# stellariscope.net
KiCad netlist of a schematic drawn in EAGLE
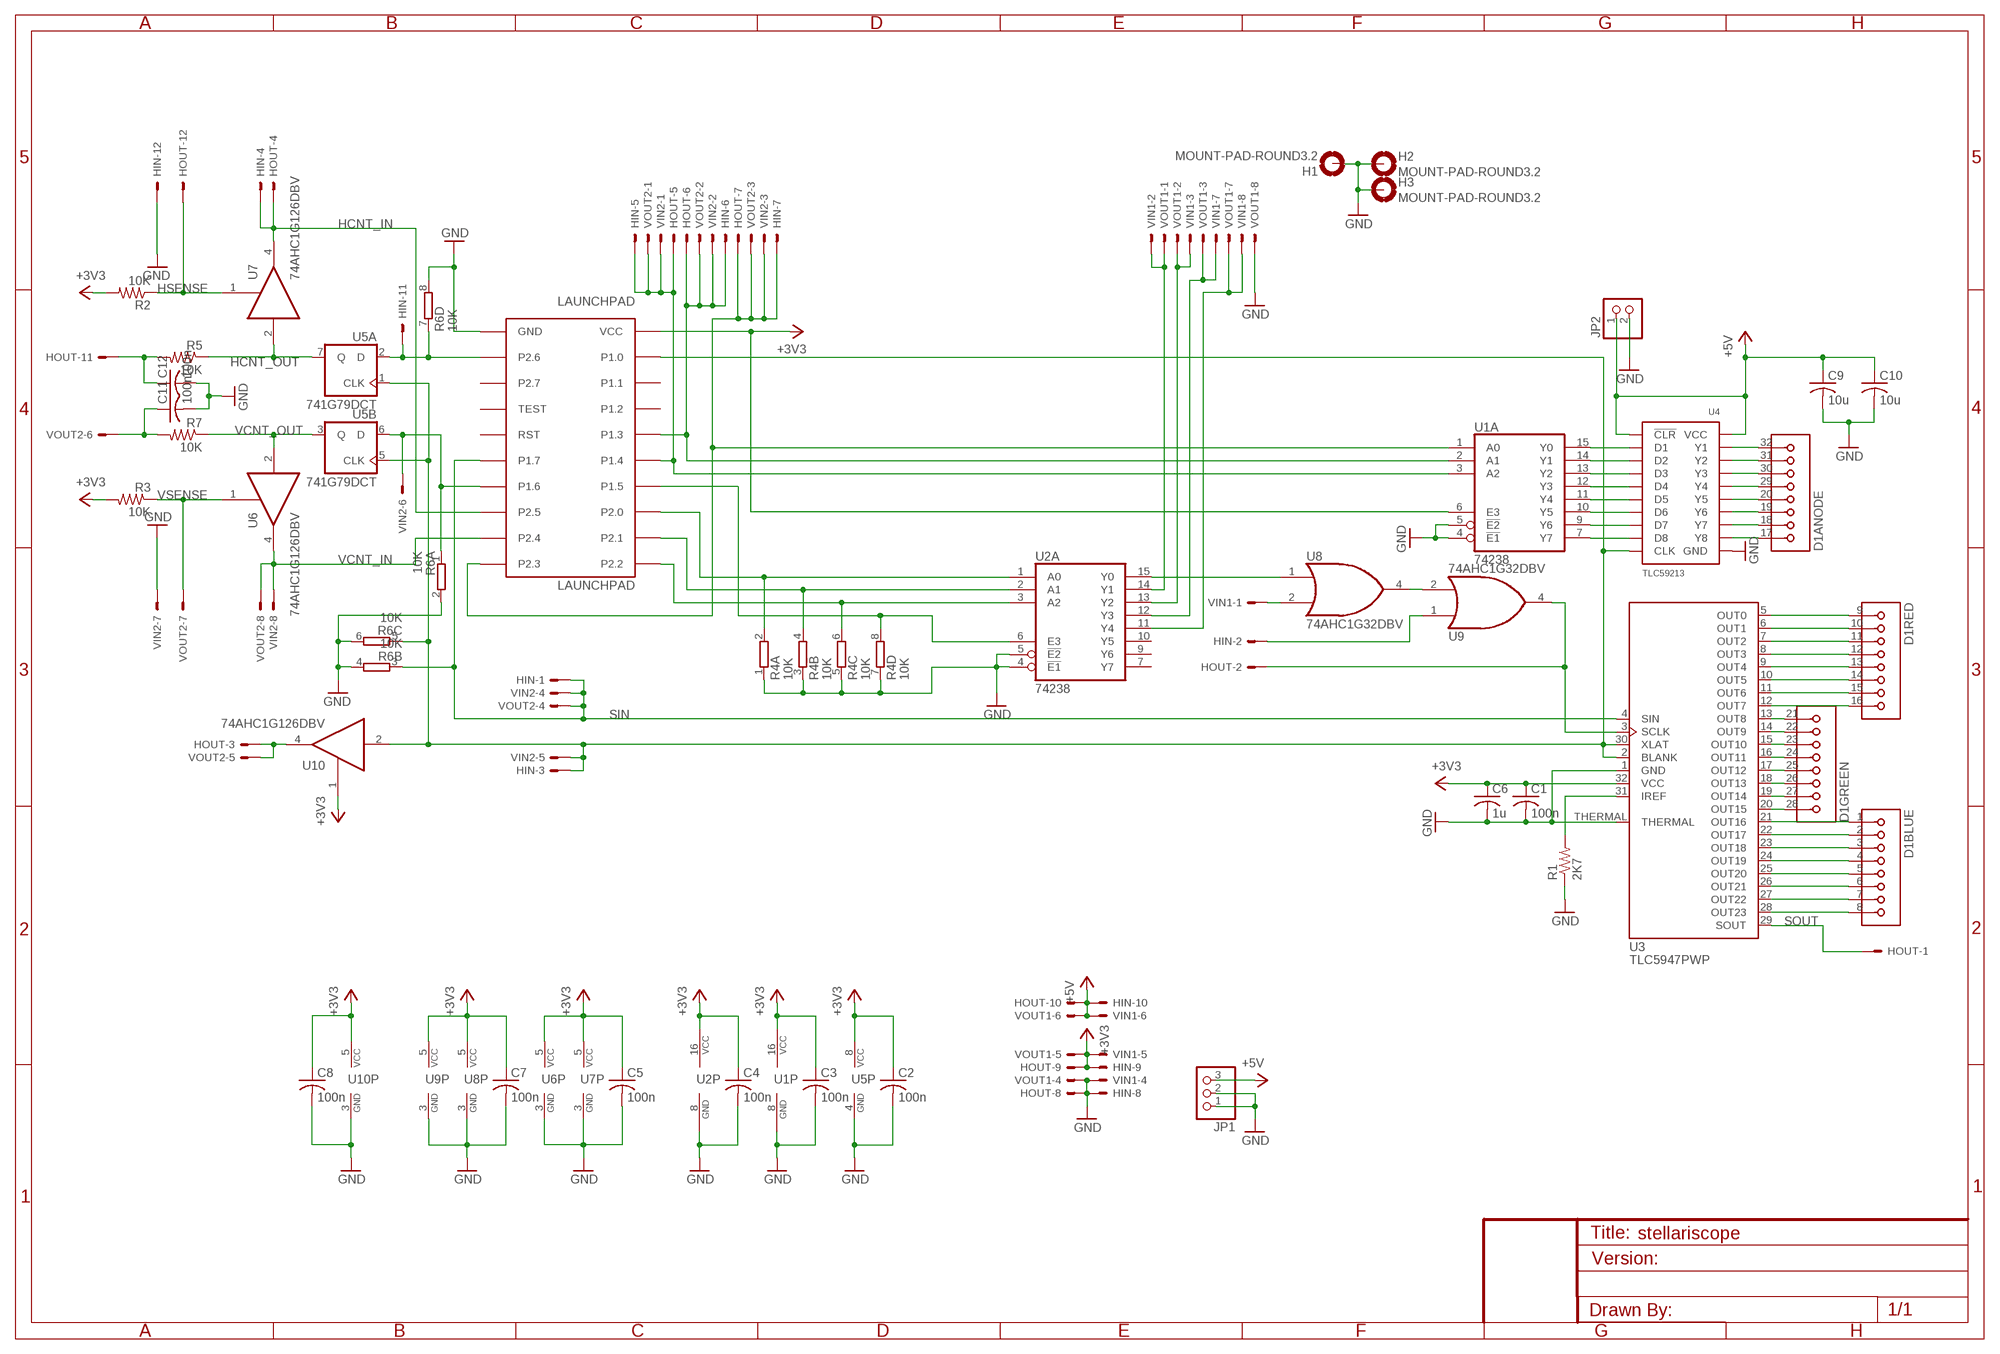
[diagram p0: schematic, sheet 1]

(export (version "E")
  (design (tool "Eeschema 10.0.6"))
  (components
    (comp (ref "C1")
      (value "100n")
      (footprint "eagle-import:C0603")
      (fields (field (name "PARTNO") "CC0603KRX7R9BB104"))
      (libsource (lib "eagle-import") (part "C-USC0603"))
    )
    (comp (ref "C2")
      (value "100n")
      (footprint "eagle-import:C0603")
      (fields (field (name "PARTNO") "CC0603KRX7R9BB104"))
      (libsource (lib "eagle-import") (part "C-USC0603"))
    )
    (comp (ref "C3")
      (value "100n")
      (footprint "eagle-import:C0603")
      (fields (field (name "PARTNO") "CC0603KRX7R9BB104"))
      (libsource (lib "eagle-import") (part "C-USC0603"))
    )
    (comp (ref "C4")
      (value "100n")
      (footprint "eagle-import:C0603")
      (fields (field (name "PARTNO") "CC0603KRX7R9BB104"))
      (libsource (lib "eagle-import") (part "C-USC0603"))
    )
    (comp (ref "C5")
      (value "100n")
      (footprint "eagle-import:C0603")
      (fields (field (name "PARTNO") "CC0603KRX7R9BB104"))
      (libsource (lib "eagle-import") (part "C-USC0603"))
    )
    (comp (ref "C6")
      (value "1u")
      (footprint "eagle-import:C0603")
      (fields (field (name "PARTNO") "C1608X5R1E105M"))
      (libsource (lib "eagle-import") (part "C-USC0603"))
    )
    (comp (ref "C7")
      (value "100n")
      (footprint "eagle-import:C0603")
      (fields (field (name "PARTNO") "CC0603KRX7R9BB104"))
      (libsource (lib "eagle-import") (part "C-USC0603"))
    )
    (comp (ref "C8")
      (value "100n")
      (footprint "eagle-import:C0603")
      (fields (field (name "PARTNO") "CC0603KRX7R9BB104"))
      (libsource (lib "eagle-import") (part "C-USC0603"))
    )
    (comp (ref "C9")
      (value "10u")
      (footprint "eagle-import:C1210")
      (fields (field (name "PARTNO") "C3216X5R1E106M"))
      (libsource (lib "eagle-import") (part "C-USC1210"))
    )
    (comp (ref "C10")
      (value "10u")
      (footprint "eagle-import:C1210")
      (fields (field (name "PARTNO") "C3216X5R1E106M"))
      (libsource (lib "eagle-import") (part "C-USC1210"))
    )
    (comp (ref "C11")
      (value "100n")
      (footprint "eagle-import:C0603")
      (fields (field (name "PARTNO") "CC0603KRX7R9BB104"))
      (libsource (lib "eagle-import") (part "C-USC0603"))
    )
    (comp (ref "C12")
      (value "100n")
      (footprint "eagle-import:C0603")
      (fields (field (name "PARTNO") "CC0603KRX7R9BB104"))
      (libsource (lib "eagle-import") (part "C-USC0603"))
    )
    (comp (ref "D1")
      (value "60MM-8X8-RGB-LED-ARRAY")
      (footprint "eagle-import:60MM-8X8-RGB-MATRIX")
      (fields (field (name "BOM") "EXCLUDE") (field (name "PARTNO") "*"))
      (libsource (lib "eagle-import") (part "60MM-8X8-RGB-LED-ARRAY"))
    )
    (comp (ref "H1")
      (value "MOUNT-PAD-ROUND3.2")
      (footprint "eagle-import:3,2-PAD")
      (libsource (lib "eagle-import") (part "MOUNT-PAD-ROUND3.2"))
    )
    (comp (ref "H2")
      (value "MOUNT-PAD-ROUND3.2")
      (footprint "eagle-import:3,2-PAD")
      (libsource (lib "eagle-import") (part "MOUNT-PAD-ROUND3.2"))
    )
    (comp (ref "H3")
      (value "MOUNT-PAD-ROUND3.2")
      (footprint "eagle-import:3,2-PAD")
      (libsource (lib "eagle-import") (part "MOUNT-PAD-ROUND3.2"))
    )
    (comp (ref "HIN")
      (value "87760-121")
      (footprint "eagle-import:87760-121")
      (fields (field (name "PARTNO") "87760-121"))
      (libsource (lib "eagle-import") (part "87760-121"))
    )
    (comp (ref "HOUT")
      (value "87264-125")
      (footprint "eagle-import:87264-125")
      (fields (field (name "PARTNO") "87264-125"))
      (libsource (lib "eagle-import") (part "87264-125"))
    )
    (comp (ref "JP1")
      (value "PINHD-1X3")
      (footprint "eagle-import:1X03")
      (libsource (lib "eagle-import") (part "PINHD-1X3"))
    )
    (comp (ref "JP2")
      (value "PINHD-1X2_2.54-90°")
      (footprint "eagle-import:1X02_90")
      (libsource (lib "eagle-import") (part "PINHD-1X2_2.54-90°"))
    )
    (comp (ref "LAUNCHPAD")
      (value "LAUNCHPAD")
      (footprint "eagle-import:LAUNCHPAD")
      (libsource (lib "eagle-import") (part "LAUNCHPAD"))
    )
    (comp (ref "R1")
      (value "2K7")
      (footprint "eagle-import:R0603")
      (fields (field (name "PARTNO") "RMCF0603FT2K70"))
      (libsource (lib "eagle-import") (part "R-US_R0603"))
    )
    (comp (ref "R2")
      (value "10K")
      (footprint "eagle-import:R0603")
      (fields (field (name "PARTNO") "RMCF0603FT10K0"))
      (libsource (lib "eagle-import") (part "R-US_R0603"))
    )
    (comp (ref "R3")
      (value "10K")
      (footprint "eagle-import:R0603")
      (fields (field (name "PARTNO") "RMCF0603FT10K0"))
      (libsource (lib "eagle-import") (part "R-US_R0603"))
    )
    (comp (ref "R4")
      (value "10K")
      (footprint "eagle-import:CTS742C083-RES")
      (fields (field (name "PARTNO") "742C083103JPTR"))
      (libsource (lib "eagle-import") (part "4R-NCTS742C083"))
    )
    (comp (ref "R5")
      (value "10K")
      (footprint "eagle-import:R0603")
      (fields (field (name "PARTNO") "RMCF0603FT10K0"))
      (libsource (lib "eagle-import") (part "R-US_R0603"))
    )
    (comp (ref "R6")
      (value "10K")
      (footprint "eagle-import:CTS742C083-RES")
      (fields (field (name "PARTNO") "742C083103JPTR"))
      (libsource (lib "eagle-import") (part "4R-NCTS742C083"))
    )
    (comp (ref "R7")
      (value "10K")
      (footprint "eagle-import:R0603")
      (fields (field (name "PARTNO") "RMCF0603FT10K0"))
      (libsource (lib "eagle-import") (part "R-US_R0603"))
    )
    (comp (ref "U1")
      (value "74238")
      (footprint "eagle-import:TSSOP16")
      (fields (field (name "PARTNO") "CD74HC238PWR"))
      (libsource (lib "eagle-import") (part "74238"))
    )
    (comp (ref "U2")
      (value "74238")
      (footprint "eagle-import:TSSOP16")
      (fields (field (name "PARTNO") "CD74HC238PWR"))
      (libsource (lib "eagle-import") (part "74238"))
    )
    (comp (ref "U3")
      (value "TLC5947PWP")
      (footprint "eagle-import:HTSSOP32-PWP")
      (fields (field (name "PARTNO") "TLC5947DAP"))
      (libsource (lib "eagle-import") (part "TLC5947PWP"))
    )
    (comp (ref "U4")
      (value "TLC59213")
      (footprint "eagle-import:TSSOP20")
      (fields (field (name "PARTNO") "TLC59213IPWR"))
      (libsource (lib "eagle-import") (part "TLC59213"))
    )
    (comp (ref "U5")
      (value "741G79DCT")
      (footprint "eagle-import:DCT_R-PDSO-G8")
      (fields (field (name "PARTNO") "SN74LVC2G79DCTR"))
      (libsource (lib "eagle-import") (part "741G79DCT"))
    )
    (comp (ref "U6")
      (value "74AHC1G126DBV")
      (footprint "eagle-import:SOT23-5")
      (fields (field (name "PARTNO") "SN74LVC1G126DBVR"))
      (libsource (lib "eagle-import") (part "741G126DBVAHC"))
    )
    (comp (ref "U7")
      (value "74AHC1G126DBV")
      (footprint "eagle-import:SOT23-5")
      (fields (field (name "PARTNO") "SN74LVC1G126DBVR"))
      (libsource (lib "eagle-import") (part "741G126DBVAHC"))
    )
    (comp (ref "U8")
      (value "74AHC1G32DBV")
      (footprint "eagle-import:SOT23-5")
      (fields (field (name "PARTNO") "SN74LVC1G32QDBVRQ1"))
      (libsource (lib "eagle-import") (part "741G32DBVAHC"))
    )
    (comp (ref "U9")
      (value "74AHC1G32DBV")
      (footprint "eagle-import:SOT23-5")
      (fields (field (name "PARTNO") "SN74LVC1G32QDBVRQ1"))
      (libsource (lib "eagle-import") (part "741G32DBVAHC"))
    )
    (comp (ref "U10")
      (value "74AHC1G126DBV")
      (footprint "eagle-import:SOT23-5")
      (fields (field (name "PARTNO") "SN74LVC1G126DBVR"))
      (libsource (lib "eagle-import") (part "741G126DBVAHC"))
    )
    (comp (ref "VIN1")
      (value "87760-081")
      (footprint "eagle-import:87760-081")
      (fields (field (name "PARTNO") "87760-081"))
      (libsource (lib "eagle-import") (part "87760-081"))
    )
    (comp (ref "VIN2")
      (value "87760-081")
      (footprint "eagle-import:87760-081")
      (fields (field (name "PARTNO") "87760-081"))
      (libsource (lib "eagle-import") (part "87760-081"))
    )
    (comp (ref "VOUT1")
      (value "87264-085")
      (footprint "eagle-import:87264-085")
      (fields (field (name "PARTNO") "87264-085"))
      (libsource (lib "eagle-import") (part "87264-085"))
    )
    (comp (ref "VOUT2")
      (value "87264-085")
      (footprint "eagle-import:87264-085")
      (fields (field (name "PARTNO") "87264-085"))
      (libsource (lib "eagle-import") (part "87264-085"))
    )
  )
  (nets
    (net (code "1") (name "+3V3") (class "Default")
      (node (ref "C1") (pin "1") (pinfunction "1_1") (pintype "passive"))
      (node (ref "C2") (pin "1") (pinfunction "1_1") (pintype "passive"))
      (node (ref "C3") (pin "1") (pinfunction "1_1") (pintype "passive"))
      (node (ref "C4") (pin "1") (pinfunction "1_1") (pintype "passive"))
      (node (ref "C5") (pin "1") (pinfunction "1_1") (pintype "passive"))
      (node (ref "C6") (pin "1") (pinfunction "1_1") (pintype "passive"))
      (node (ref "C7") (pin "1") (pinfunction "1_1") (pintype "passive"))
      (node (ref "C8") (pin "1") (pinfunction "1_1") (pintype "passive"))
      (node (ref "HIN") (pin "10") (pinfunction "S_10") (pintype "passive"))
      (node (ref "HOUT") (pin "9") (pinfunction "S_9") (pintype "passive"))
      (node (ref "LAUNCHPAD") (pin "VCC") (pinfunction "VCC_VCC") (pintype "power_in"))
      (node (ref "R2") (pin "2") (pinfunction "2_2") (pintype "passive"))
      (node (ref "R3") (pin "2") (pinfunction "2_2") (pintype "passive"))
      (node (ref "U1") (pin "16") (pinfunction "VCC_16") (pintype "power_in"))
      (node (ref "U1") (pin "6") (pinfunction "E3_6") (pintype "input"))
      (node (ref "U10") (pin "1") (pinfunction "OE_1") (pintype "input"))
      (node (ref "U10") (pin "5") (pinfunction "VCC_5") (pintype "power_in"))
      (node (ref "U2") (pin "16") (pinfunction "VCC_16") (pintype "power_in"))
      (node (ref "U3") (pin "32") (pinfunction "VCC_32") (pintype "bidirectional"))
      (node (ref "U5") (pin "8") (pinfunction "VCC_8") (pintype "power_in"))
      (node (ref "U6") (pin "5") (pinfunction "VCC_5") (pintype "power_in"))
      (node (ref "U7") (pin "5") (pinfunction "VCC_5") (pintype "power_in"))
      (node (ref "U8") (pin "5") (pinfunction "VCC_5") (pintype "power_in"))
      (node (ref "U9") (pin "5") (pinfunction "VCC_5") (pintype "power_in"))
      (node (ref "VIN1") (pin "5") (pinfunction "S_5") (pintype "passive"))
      (node (ref "VOUT1") (pin "5") (pinfunction "S_5") (pintype "passive"))
    )
    (net (code "2") (name "+5V") (class "Default")
      (node (ref "C10") (pin "1") (pinfunction "1_1") (pintype "passive"))
      (node (ref "C9") (pin "1") (pinfunction "1_1") (pintype "passive"))
      (node (ref "HIN") (pin "9") (pinfunction "S_9") (pintype "passive"))
      (node (ref "HOUT") (pin "10") (pinfunction "S_10") (pintype "passive"))
      (node (ref "JP1") (pin "3") (pinfunction "3_3") (pintype "passive"))
      (node (ref "JP2") (pin "1") (pinfunction "1_1") (pintype "passive"))
      (node (ref "U4") (pin "1") (pinfunction "~{CLR}_1") (pintype "power_in"))
      (node (ref "U4") (pin "20") (pinfunction "VCC_20") (pintype "power_in"))
      (node (ref "VIN1") (pin "6") (pinfunction "S_6") (pintype "passive"))
      (node (ref "VOUT1") (pin "6") (pinfunction "S_6") (pintype "passive"))
    )
    (net (code "3") (name "/HCNT_IN") (class "Default")
      (node (ref "HIN") (pin "4") (pinfunction "S_4") (pintype "passive"))
      (node (ref "HOUT") (pin "4") (pinfunction "S_4") (pintype "passive"))
      (node (ref "LAUNCHPAD") (pin "P2.5") (pinfunction "P2.5_P2.5") (pintype "bidirectional"))
      (node (ref "U7") (pin "4") (pinfunction "O_4") (pintype "output"))
    )
    (net (code "4") (name "/HCNT_OUT") (class "Default")
      (node (ref "R5") (pin "1") (pinfunction "1_1") (pintype "passive"))
      (node (ref "U5") (pin "7") (pinfunction "Q_7") (pintype "output"))
      (node (ref "U7") (pin "2") (pinfunction "I_2") (pintype "input"))
    )
    (net (code "5") (name "/HSENSE") (class "Default")
      (node (ref "HOUT") (pin "12") (pinfunction "S_12") (pintype "passive"))
      (node (ref "R2") (pin "1") (pinfunction "1_1") (pintype "passive"))
      (node (ref "U7") (pin "1") (pinfunction "OE_1") (pintype "input"))
    )
    (net (code "6") (name "/SIN") (class "Default")
      (node (ref "HIN") (pin "1") (pinfunction "S_1") (pintype "passive"))
      (node (ref "LAUNCHPAD") (pin "P1.7") (pinfunction "P1.7_P1.7") (pintype "bidirectional"))
      (node (ref "R6") (pin "3") (pinfunction "1_3") (pintype "passive"))
      (node (ref "U3") (pin "4") (pinfunction "SIN_4") (pintype "bidirectional"))
      (node (ref "VIN2") (pin "4") (pinfunction "S_4") (pintype "passive"))
      (node (ref "VOUT2") (pin "4") (pinfunction "S_4") (pintype "passive"))
    )
    (net (code "7") (name "/SOUT") (class "Default")
      (node (ref "HOUT") (pin "1") (pinfunction "S_1") (pintype "passive"))
      (node (ref "U3") (pin "29") (pinfunction "SOUT_29") (pintype "bidirectional"))
    )
    (net (code "8") (name "/VCNT_IN") (class "Default")
      (node (ref "LAUNCHPAD") (pin "P2.4") (pinfunction "P2.4_P2.4") (pintype "bidirectional"))
      (node (ref "U6") (pin "4") (pinfunction "O_4") (pintype "output"))
      (node (ref "VIN2") (pin "8") (pinfunction "S_8") (pintype "passive"))
      (node (ref "VOUT2") (pin "8") (pinfunction "S_8") (pintype "passive"))
    )
    (net (code "9") (name "/VCNT_OUT") (class "Default")
      (node (ref "R7") (pin "1") (pinfunction "1_1") (pintype "passive"))
      (node (ref "U5") (pin "3") (pinfunction "Q_3") (pintype "output"))
      (node (ref "U6") (pin "2") (pinfunction "I_2") (pintype "input"))
    )
    (net (code "10") (name "/VSENSE") (class "Default")
      (node (ref "R3") (pin "1") (pinfunction "1_1") (pintype "passive"))
      (node (ref "U6") (pin "1") (pinfunction "OE_1") (pintype "input"))
      (node (ref "VOUT2") (pin "7") (pinfunction "S_7") (pintype "passive"))
    )
    (net (code "11") (name "GND") (class "Default")
      (node (ref "C1") (pin "2") (pinfunction "2_2") (pintype "passive"))
      (node (ref "C10") (pin "2") (pinfunction "2_2") (pintype "passive"))
      (node (ref "C11") (pin "2") (pinfunction "2_2") (pintype "passive"))
      (node (ref "C12") (pin "2") (pinfunction "2_2") (pintype "passive"))
      (node (ref "C2") (pin "2") (pinfunction "2_2") (pintype "passive"))
      (node (ref "C3") (pin "2") (pinfunction "2_2") (pintype "passive"))
      (node (ref "C4") (pin "2") (pinfunction "2_2") (pintype "passive"))
      (node (ref "C5") (pin "2") (pinfunction "2_2") (pintype "passive"))
      (node (ref "C6") (pin "2") (pinfunction "2_2") (pintype "passive"))
      (node (ref "C7") (pin "2") (pinfunction "2_2") (pintype "passive"))
      (node (ref "C8") (pin "2") (pinfunction "2_2") (pintype "passive"))
      (node (ref "C9") (pin "2") (pinfunction "2_2") (pintype "passive"))
      (node (ref "H1") (pin "B3,2") (pinfunction "MOUNT_B3,2") (pintype "passive"))
      (node (ref "H2") (pin "B3,2") (pinfunction "MOUNT_B3,2") (pintype "passive"))
      (node (ref "H3") (pin "B3,2") (pinfunction "MOUNT_B3,2") (pintype "passive"))
      (node (ref "HIN") (pin "12") (pinfunction "S_12") (pintype "passive"))
      (node (ref "HIN") (pin "8") (pinfunction "S_8") (pintype "passive"))
      (node (ref "HOUT") (pin "8") (pinfunction "S_8") (pintype "passive"))
      (node (ref "JP1") (pin "1") (pinfunction "1_1") (pintype "passive"))
      (node (ref "JP1") (pin "2") (pinfunction "2_2") (pintype "passive"))
      (node (ref "JP2") (pin "2") (pinfunction "2_2") (pintype "passive"))
      (node (ref "LAUNCHPAD") (pin "GND") (pinfunction "GND_GND") (pintype "power_in"))
      (node (ref "R1") (pin "1") (pinfunction "1_1") (pintype "passive"))
      (node (ref "R4") (pin "1") (pinfunction "1_1") (pintype "passive"))
      (node (ref "R4") (pin "3") (pinfunction "1_3") (pintype "passive"))
      (node (ref "R4") (pin "5") (pinfunction "1_5") (pintype "passive"))
      (node (ref "R4") (pin "7") (pinfunction "1_7") (pintype "passive"))
      (node (ref "R6") (pin "2") (pinfunction "2_2") (pintype "passive"))
      (node (ref "R6") (pin "4") (pinfunction "2_4") (pintype "passive"))
      (node (ref "R6") (pin "6") (pinfunction "2_6") (pintype "passive"))
      (node (ref "R6") (pin "8") (pinfunction "2_8") (pintype "passive"))
      (node (ref "U1") (pin "4") (pinfunction "~{E1}_4") (pintype "input"))
      (node (ref "U1") (pin "5") (pinfunction "~{E2}_5") (pintype "input"))
      (node (ref "U1") (pin "8") (pinfunction "GND_8") (pintype "power_in"))
      (node (ref "U10") (pin "3") (pinfunction "GND_3") (pintype "power_in"))
      (node (ref "U2") (pin "4") (pinfunction "~{E1}_4") (pintype "input"))
      (node (ref "U2") (pin "5") (pinfunction "~{E2}_5") (pintype "input"))
      (node (ref "U2") (pin "8") (pinfunction "GND_8") (pintype "power_in"))
      (node (ref "U3") (pin "1") (pinfunction "GND_1") (pintype "bidirectional"))
      (node (ref "U3") (pin "THERMAL") (pinfunction "THERMAL_THERMAL") (pintype "bidirectional"))
      (node (ref "U4") (pin "11") (pinfunction "GND_11") (pintype "power_in"))
      (node (ref "U5") (pin "4") (pinfunction "GND_4") (pintype "power_in"))
      (node (ref "U6") (pin "3") (pinfunction "GND_3") (pintype "power_in"))
      (node (ref "U7") (pin "3") (pinfunction "GND_3") (pintype "power_in"))
      (node (ref "U8") (pin "3") (pinfunction "GND_3") (pintype "power_in"))
      (node (ref "U9") (pin "3") (pinfunction "GND_3") (pintype "power_in"))
      (node (ref "VIN1") (pin "4") (pinfunction "S_4") (pintype "passive"))
      (node (ref "VIN2") (pin "7") (pinfunction "S_7") (pintype "passive"))
      (node (ref "VOUT1") (pin "4") (pinfunction "S_4") (pintype "passive"))
      (node (ref "VOUT1") (pin "8") (pinfunction "S_8") (pintype "passive"))
    )
    (net (code "12") (name "Net-(D1A-1)") (class "Default")
      (node (ref "D1") (pin "17") (pinfunction "1_17") (pintype "bidirectional"))
      (node (ref "U4") (pin "12") (pinfunction "Y8_12") (pintype "power_in"))
    )
    (net (code "13") (name "Net-(D1A-2)") (class "Default")
      (node (ref "D1") (pin "18") (pinfunction "2_18") (pintype "bidirectional"))
      (node (ref "U4") (pin "13") (pinfunction "Y7_13") (pintype "power_in"))
    )
    (net (code "14") (name "Net-(D1A-3)") (class "Default")
      (node (ref "D1") (pin "19") (pinfunction "3_19") (pintype "bidirectional"))
      (node (ref "U4") (pin "14") (pinfunction "Y6_14") (pintype "power_in"))
    )
    (net (code "15") (name "Net-(D1A-4)") (class "Default")
      (node (ref "D1") (pin "20") (pinfunction "4_20") (pintype "bidirectional"))
      (node (ref "U4") (pin "15") (pinfunction "Y5_15") (pintype "power_in"))
    )
    (net (code "16") (name "Net-(D1A-5)") (class "Default")
      (node (ref "D1") (pin "29") (pinfunction "5_29") (pintype "bidirectional"))
      (node (ref "U4") (pin "16") (pinfunction "Y4_16") (pintype "power_in"))
    )
    (net (code "17") (name "Net-(D1A-6)") (class "Default")
      (node (ref "D1") (pin "30") (pinfunction "6_30") (pintype "bidirectional"))
      (node (ref "U4") (pin "17") (pinfunction "Y3_17") (pintype "power_in"))
    )
    (net (code "18") (name "Net-(D1A-7)") (class "Default")
      (node (ref "D1") (pin "31") (pinfunction "7_31") (pintype "bidirectional"))
      (node (ref "U4") (pin "18") (pinfunction "Y2_18") (pintype "power_in"))
    )
    (net (code "19") (name "Net-(D1A-8)") (class "Default")
      (node (ref "D1") (pin "32") (pinfunction "8_32") (pintype "bidirectional"))
      (node (ref "U4") (pin "19") (pinfunction "Y1_19") (pintype "power_in"))
    )
    (net (code "20") (name "Net-(D1C-1)") (class "Default")
      (node (ref "D1") (pin "28") (pinfunction "1_28") (pintype "bidirectional"))
      (node (ref "U3") (pin "20") (pinfunction "OUT15_20") (pintype "bidirectional"))
    )
    (net (code "21") (name "Net-(D1C-2)") (class "Default")
      (node (ref "D1") (pin "27") (pinfunction "2_27") (pintype "bidirectional"))
      (node (ref "U3") (pin "19") (pinfunction "OUT14_19") (pintype "bidirectional"))
    )
    (net (code "22") (name "Net-(D1C-3)") (class "Default")
      (node (ref "D1") (pin "26") (pinfunction "3_26") (pintype "bidirectional"))
      (node (ref "U3") (pin "18") (pinfunction "OUT13_18") (pintype "bidirectional"))
    )
    (net (code "23") (name "Net-(D1C-4)") (class "Default")
      (node (ref "D1") (pin "25") (pinfunction "4_25") (pintype "bidirectional"))
      (node (ref "U3") (pin "17") (pinfunction "OUT12_17") (pintype "bidirectional"))
    )
    (net (code "24") (name "Net-(D1C-5)") (class "Default")
      (node (ref "D1") (pin "24") (pinfunction "5_24") (pintype "bidirectional"))
      (node (ref "U3") (pin "16") (pinfunction "OUT11_16") (pintype "bidirectional"))
    )
    (net (code "25") (name "Net-(D1C-6)") (class "Default")
      (node (ref "D1") (pin "23") (pinfunction "6_23") (pintype "bidirectional"))
      (node (ref "U3") (pin "15") (pinfunction "OUT10_15") (pintype "bidirectional"))
    )
    (net (code "26") (name "Net-(D1C-7)") (class "Default")
      (node (ref "D1") (pin "22") (pinfunction "7_22") (pintype "bidirectional"))
      (node (ref "U3") (pin "14") (pinfunction "OUT9_14") (pintype "bidirectional"))
    )
    (net (code "27") (name "Net-(D1C-8)") (class "Default")
      (node (ref "D1") (pin "21") (pinfunction "8_21") (pintype "bidirectional"))
      (node (ref "U3") (pin "13") (pinfunction "OUT8_13") (pintype "bidirectional"))
    )
    (net (code "28") (name "Net-(D1D-1)") (class "Default")
      (node (ref "D1") (pin "9") (pinfunction "1_9") (pintype "bidirectional"))
      (node (ref "U3") (pin "5") (pinfunction "OUT0_5") (pintype "bidirectional"))
    )
    (net (code "29") (name "Net-(D1D-2)") (class "Default")
      (node (ref "D1") (pin "10") (pinfunction "2_10") (pintype "bidirectional"))
      (node (ref "U3") (pin "6") (pinfunction "OUT1_6") (pintype "bidirectional"))
    )
    (net (code "30") (name "Net-(D1D-3)") (class "Default")
      (node (ref "D1") (pin "11") (pinfunction "3_11") (pintype "bidirectional"))
      (node (ref "U3") (pin "7") (pinfunction "OUT2_7") (pintype "bidirectional"))
    )
    (net (code "31") (name "Net-(D1D-4)") (class "Default")
      (node (ref "D1") (pin "12") (pinfunction "4_12") (pintype "bidirectional"))
      (node (ref "U3") (pin "8") (pinfunction "OUT3_8") (pintype "bidirectional"))
    )
    (net (code "32") (name "Net-(D1D-5)") (class "Default")
      (node (ref "D1") (pin "13") (pinfunction "5_13") (pintype "bidirectional"))
      (node (ref "U3") (pin "9") (pinfunction "OUT4_9") (pintype "bidirectional"))
    )
    (net (code "33") (name "Net-(D1D-6)") (class "Default")
      (node (ref "D1") (pin "14") (pinfunction "6_14") (pintype "bidirectional"))
      (node (ref "U3") (pin "10") (pinfunction "OUT5_10") (pintype "bidirectional"))
    )
    (net (code "34") (name "Net-(D1D-7)") (class "Default")
      (node (ref "D1") (pin "15") (pinfunction "7_15") (pintype "bidirectional"))
      (node (ref "U3") (pin "11") (pinfunction "OUT6_11") (pintype "bidirectional"))
    )
    (net (code "35") (name "Net-(D1D-8)") (class "Default")
      (node (ref "D1") (pin "16") (pinfunction "8_16") (pintype "bidirectional"))
      (node (ref "U3") (pin "12") (pinfunction "OUT7_12") (pintype "bidirectional"))
    )
    (net (code "36") (name "Net-(HINC-S)") (class "Default")
      (node (ref "HIN") (pin "11") (pinfunction "S_11") (pintype "passive"))
      (node (ref "LAUNCHPAD") (pin "P2.6") (pinfunction "P2.6_P2.6") (pintype "bidirectional"))
      (node (ref "R6") (pin "7") (pinfunction "1_7") (pintype "passive"))
      (node (ref "U5") (pin "2") (pinfunction "D_2") (pintype "input"))
    )
    (net (code "37") (name "Net-(HINE-S)") (class "Default")
      (node (ref "HIN") (pin "2") (pinfunction "S_2") (pintype "passive"))
      (node (ref "U9") (pin "1") (pinfunction "I0_1") (pintype "input"))
    )
    (net (code "38") (name "Net-(HINF-S)") (class "Default")
      (node (ref "HIN") (pin "3") (pinfunction "S_3") (pintype "passive"))
      (node (ref "LAUNCHPAD") (pin "P1.0") (pinfunction "P1.0_P1.0") (pintype "bidirectional"))
      (node (ref "R6") (pin "5") (pinfunction "1_5") (pintype "passive"))
      (node (ref "U10") (pin "2") (pinfunction "I_2") (pintype "input"))
      (node (ref "U3") (pin "2") (pinfunction "BLANK_2") (pintype "bidirectional"))
      (node (ref "U3") (pin "30") (pinfunction "XLAT_30") (pintype "bidirectional"))
      (node (ref "U4") (pin "10") (pinfunction "CLK_10") (pintype "power_in"))
      (node (ref "U5") (pin "1") (pinfunction "CLK_1") (pintype "input"))
      (node (ref "U5") (pin "5") (pinfunction "CLK_5") (pintype "input"))
      (node (ref "VIN2") (pin "5") (pinfunction "S_5") (pintype "passive"))
    )
    (net (code "39") (name "Net-(HINH-S)") (class "Default")
      (node (ref "HIN") (pin "5") (pinfunction "S_5") (pintype "passive"))
      (node (ref "HOUT") (pin "5") (pinfunction "S_5") (pintype "passive"))
      (node (ref "LAUNCHPAD") (pin "P1.4") (pinfunction "P1.4_P1.4") (pintype "bidirectional"))
      (node (ref "U1") (pin "3") (pinfunction "A2_3") (pintype "input"))
      (node (ref "VIN2") (pin "1") (pinfunction "S_1") (pintype "passive"))
      (node (ref "VOUT2") (pin "1") (pinfunction "S_1") (pintype "passive"))
    )
    (net (code "40") (name "Net-(HINI-S)") (class "Default")
      (node (ref "HIN") (pin "6") (pinfunction "S_6") (pintype "passive"))
      (node (ref "HOUT") (pin "6") (pinfunction "S_6") (pintype "passive"))
      (node (ref "LAUNCHPAD") (pin "P1.3") (pinfunction "P1.3_P1.3") (pintype "bidirectional"))
      (node (ref "U1") (pin "2") (pinfunction "A1_2") (pintype "input"))
      (node (ref "VIN2") (pin "2") (pinfunction "S_2") (pintype "passive"))
      (node (ref "VOUT2") (pin "2") (pinfunction "S_2") (pintype "passive"))
    )
    (net (code "41") (name "Net-(HINJ-S)") (class "Default")
      (node (ref "HIN") (pin "7") (pinfunction "S_7") (pintype "passive"))
      (node (ref "HOUT") (pin "7") (pinfunction "S_7") (pintype "passive"))
      (node (ref "LAUNCHPAD") (pin "P2.3") (pinfunction "P2.3_P2.3") (pintype "bidirectional"))
      (node (ref "U1") (pin "1") (pinfunction "A0_1") (pintype "input"))
      (node (ref "VIN2") (pin "3") (pinfunction "S_3") (pintype "passive"))
      (node (ref "VOUT2") (pin "3") (pinfunction "S_3") (pintype "passive"))
    )
    (net (code "42") (name "Net-(HOUTC-S)") (class "Default")
      (node (ref "C12") (pin "1") (pinfunction "1_1") (pintype "passive"))
      (node (ref "HOUT") (pin "11") (pinfunction "S_11") (pintype "passive"))
      (node (ref "R5") (pin "2") (pinfunction "2_2") (pintype "passive"))
    )
    (net (code "43") (name "Net-(HOUTE-S)") (class "Default")
      (node (ref "HOUT") (pin "2") (pinfunction "S_2") (pintype "passive"))
      (node (ref "U3") (pin "3") (pinfunction "SCLK_3") (pintype "bidirectional"))
      (node (ref "U9") (pin "4") (pinfunction "O_4") (pintype "output"))
    )
    (net (code "44") (name "Net-(HOUTF-S)") (class "Default")
      (node (ref "HOUT") (pin "3") (pinfunction "S_3") (pintype "passive"))
      (node (ref "U10") (pin "4") (pinfunction "O_4") (pintype "output"))
      (node (ref "VOUT2") (pin "5") (pinfunction "S_5") (pintype "passive"))
    )
    (net (code "45") (name "Net-(R4B-2)") (class "Default")
      (node (ref "LAUNCHPAD") (pin "P2.1") (pinfunction "P2.1_P2.1") (pintype "bidirectional"))
      (node (ref "R4") (pin "4") (pinfunction "2_4") (pintype "passive"))
      (node (ref "U2") (pin "2") (pinfunction "A1_2") (pintype "input"))
    )
    (net (code "46") (name "Net-(R4C-2)") (class "Default")
      (node (ref "LAUNCHPAD") (pin "P2.2") (pinfunction "P2.2_P2.2") (pintype "bidirectional"))
      (node (ref "R4") (pin "6") (pinfunction "2_6") (pintype "passive"))
      (node (ref "U2") (pin "3") (pinfunction "A2_3") (pintype "input"))
    )
    (net (code "47") (name "Net-(R4D-2)") (class "Default")
      (node (ref "LAUNCHPAD") (pin "P1.5") (pinfunction "P1.5_P1.5") (pintype "bidirectional"))
      (node (ref "R4") (pin "8") (pinfunction "2_8") (pintype "passive"))
      (node (ref "U2") (pin "6") (pinfunction "E3_6") (pintype "input"))
    )
    (net (code "48") (name "Net-(U1A-Y0)") (class "Default")
      (node (ref "U1") (pin "15") (pinfunction "Y0_15") (pintype "output"))
      (node (ref "U4") (pin "2") (pinfunction "D1_2") (pintype "power_in"))
    )
    (net (code "49") (name "Net-(U1A-Y1)") (class "Default")
      (node (ref "U1") (pin "14") (pinfunction "Y1_14") (pintype "output"))
      (node (ref "U4") (pin "3") (pinfunction "D2_3") (pintype "power_in"))
    )
    (net (code "50") (name "Net-(U1A-Y2)") (class "Default")
      (node (ref "U1") (pin "13") (pinfunction "Y2_13") (pintype "output"))
      (node (ref "U4") (pin "4") (pinfunction "D3_4") (pintype "power_in"))
    )
    (net (code "51") (name "Net-(U1A-Y3)") (class "Default")
      (node (ref "U1") (pin "12") (pinfunction "Y3_12") (pintype "output"))
      (node (ref "U4") (pin "5") (pinfunction "D4_5") (pintype "power_in"))
    )
    (net (code "52") (name "Net-(U1A-Y4)") (class "Default")
      (node (ref "U1") (pin "11") (pinfunction "Y4_11") (pintype "output"))
      (node (ref "U4") (pin "6") (pinfunction "D5_6") (pintype "power_in"))
    )
    (net (code "53") (name "Net-(U1A-Y5)") (class "Default")
      (node (ref "U1") (pin "10") (pinfunction "Y5_10") (pintype "output"))
      (node (ref "U4") (pin "7") (pinfunction "D6_7") (pintype "power_in"))
    )
    (net (code "54") (name "Net-(U1A-Y6)") (class "Default")
      (node (ref "U1") (pin "9") (pinfunction "Y6_9") (pintype "output"))
      (node (ref "U4") (pin "8") (pinfunction "D7_8") (pintype "power_in"))
    )
    (net (code "55") (name "Net-(U1A-Y7)") (class "Default")
      (node (ref "U1") (pin "7") (pinfunction "Y7_7") (pintype "output"))
      (node (ref "U4") (pin "9") (pinfunction "D8_9") (pintype "power_in"))
    )
    (net (code "56") (name "Net-(U2A-A0)") (class "Default")
      (node (ref "LAUNCHPAD") (pin "P2.0") (pinfunction "P2.0_P2.0") (pintype "bidirectional"))
      (node (ref "R4") (pin "2") (pinfunction "2_2") (pintype "passive"))
      (node (ref "U2") (pin "1") (pinfunction "A0_1") (pintype "input"))
    )
    (net (code "57") (name "Net-(U2A-Y0)") (class "Default")
      (node (ref "U2") (pin "15") (pinfunction "Y0_15") (pintype "output"))
      (node (ref "U8") (pin "1") (pinfunction "I0_1") (pintype "input"))
    )
    (net (code "58") (name "Net-(U2A-Y1)") (class "Default")
      (node (ref "U2") (pin "14") (pinfunction "Y1_14") (pintype "output"))
      (node (ref "VIN1") (pin "2") (pinfunction "S_2") (pintype "passive"))
      (node (ref "VOUT1") (pin "1") (pinfunction "S_1") (pintype "passive"))
    )
    (net (code "59") (name "Net-(U2A-Y2)") (class "Default")
      (node (ref "U2") (pin "13") (pinfunction "Y2_13") (pintype "output"))
      (node (ref "VIN1") (pin "3") (pinfunction "S_3") (pintype "passive"))
      (node (ref "VOUT1") (pin "2") (pinfunction "S_2") (pintype "passive"))
    )
    (net (code "60") (name "Net-(U2A-Y3)") (class "Default")
      (node (ref "U2") (pin "12") (pinfunction "Y3_12") (pintype "output"))
      (node (ref "VIN1") (pin "7") (pinfunction "S_7") (pintype "passive"))
      (node (ref "VOUT1") (pin "3") (pinfunction "S_3") (pintype "passive"))
    )
    (net (code "61") (name "Net-(U2A-Y4)") (class "Default")
      (node (ref "U2") (pin "11") (pinfunction "Y4_11") (pintype "output"))
      (node (ref "VIN1") (pin "8") (pinfunction "S_8") (pintype "passive"))
      (node (ref "VOUT1") (pin "7") (pinfunction "S_7") (pintype "passive"))
    )
    (net (code "62") (name "Net-(U3-IREF)") (class "Default")
      (node (ref "R1") (pin "2") (pinfunction "2_2") (pintype "passive"))
      (node (ref "U3") (pin "31") (pinfunction "IREF_31") (pintype "bidirectional"))
    )
    (net (code "63") (name "Net-(U3-OUT16)") (class "Default")
      (node (ref "D1") (pin "1") (pinfunction "1_1") (pintype "bidirectional"))
      (node (ref "U3") (pin "21") (pinfunction "OUT16_21") (pintype "bidirectional"))
    )
    (net (code "64") (name "Net-(U3-OUT17)") (class "Default")
      (node (ref "D1") (pin "2") (pinfunction "2_2") (pintype "bidirectional"))
      (node (ref "U3") (pin "22") (pinfunction "OUT17_22") (pintype "bidirectional"))
    )
    (net (code "65") (name "Net-(U3-OUT18)") (class "Default")
      (node (ref "D1") (pin "3") (pinfunction "3_3") (pintype "bidirectional"))
      (node (ref "U3") (pin "23") (pinfunction "OUT18_23") (pintype "bidirectional"))
    )
    (net (code "66") (name "Net-(U3-OUT19)") (class "Default")
      (node (ref "D1") (pin "4") (pinfunction "4_4") (pintype "bidirectional"))
      (node (ref "U3") (pin "24") (pinfunction "OUT19_24") (pintype "bidirectional"))
    )
    (net (code "67") (name "Net-(U3-OUT20)") (class "Default")
      (node (ref "D1") (pin "5") (pinfunction "5_5") (pintype "bidirectional"))
      (node (ref "U3") (pin "25") (pinfunction "OUT20_25") (pintype "bidirectional"))
    )
    (net (code "68") (name "Net-(U3-OUT21)") (class "Default")
      (node (ref "D1") (pin "6") (pinfunction "6_6") (pintype "bidirectional"))
      (node (ref "U3") (pin "26") (pinfunction "OUT21_26") (pintype "bidirectional"))
    )
    (net (code "69") (name "Net-(U3-OUT22)") (class "Default")
      (node (ref "D1") (pin "7") (pinfunction "7_7") (pintype "bidirectional"))
      (node (ref "U3") (pin "27") (pinfunction "OUT22_27") (pintype "bidirectional"))
    )
    (net (code "70") (name "Net-(U3-OUT23)") (class "Default")
      (node (ref "D1") (pin "8") (pinfunction "8_8") (pintype "bidirectional"))
      (node (ref "U3") (pin "28") (pinfunction "OUT23_28") (pintype "bidirectional"))
    )
    (net (code "71") (name "Net-(U5B-D)") (class "Default")
      (node (ref "LAUNCHPAD") (pin "P1.6") (pinfunction "P1.6_P1.6") (pintype "bidirectional"))
      (node (ref "R6") (pin "1") (pinfunction "1_1") (pintype "passive"))
      (node (ref "U5") (pin "6") (pinfunction "D_6") (pintype "input"))
      (node (ref "VIN2") (pin "6") (pinfunction "S_6") (pintype "passive"))
    )
    (net (code "72") (name "Net-(U8A-I1)") (class "Default")
      (node (ref "U8") (pin "2") (pinfunction "I1_2") (pintype "input"))
      (node (ref "VIN1") (pin "1") (pinfunction "S_1") (pintype "passive"))
    )
    (net (code "73") (name "Net-(U8A-O)") (class "Default")
      (node (ref "U8") (pin "4") (pinfunction "O_4") (pintype "output"))
      (node (ref "U9") (pin "2") (pinfunction "I1_2") (pintype "input"))
    )
    (net (code "74") (name "Net-(VOUT2F-S)") (class "Default")
      (node (ref "C11") (pin "1") (pinfunction "1_1") (pintype "passive"))
      (node (ref "R7") (pin "2") (pinfunction "2_2") (pintype "passive"))
      (node (ref "VOUT2") (pin "6") (pinfunction "S_6") (pintype "passive"))
    )
    (net (code "75") (name "unconnected-(LAUNCHPAD-PadP1.1)") (class "Default")
      (node (ref "LAUNCHPAD") (pin "P1.1") (pinfunction "P1.1_P1.1") (pintype "bidirectional"))
    )
    (net (code "76") (name "unconnected-(LAUNCHPAD-PadP1.2)") (class "Default")
      (node (ref "LAUNCHPAD") (pin "P1.2") (pinfunction "P1.2_P1.2") (pintype "bidirectional"))
    )
    (net (code "77") (name "unconnected-(LAUNCHPAD-PadP2.7)") (class "Default")
      (node (ref "LAUNCHPAD") (pin "P2.7") (pinfunction "P2.7_P2.7") (pintype "bidirectional"))
    )
    (net (code "78") (name "unconnected-(LAUNCHPAD-PadRST)") (class "Default")
      (node (ref "LAUNCHPAD") (pin "RST") (pinfunction "RST_RST") (pintype "bidirectional"))
    )
    (net (code "79") (name "unconnected-(LAUNCHPAD-PadTEST)") (class "Default")
      (node (ref "LAUNCHPAD") (pin "TEST") (pinfunction "TEST_TEST") (pintype "bidirectional"))
    )
    (net (code "80") (name "unconnected-(U2A-Y5-Pad10)") (class "Default")
      (node (ref "U2") (pin "10") (pinfunction "Y5_10") (pintype "output"))
    )
    (net (code "81") (name "unconnected-(U2A-Y6-Pad9)") (class "Default")
      (node (ref "U2") (pin "9") (pinfunction "Y6_9") (pintype "output"))
    )
    (net (code "82") (name "unconnected-(U2A-Y7-Pad7)") (class "Default")
      (node (ref "U2") (pin "7") (pinfunction "Y7_7") (pintype "output"))
    )
  )
)
